# Mp100.net
KiCad netlist of a schematic drawn in Altium Designer
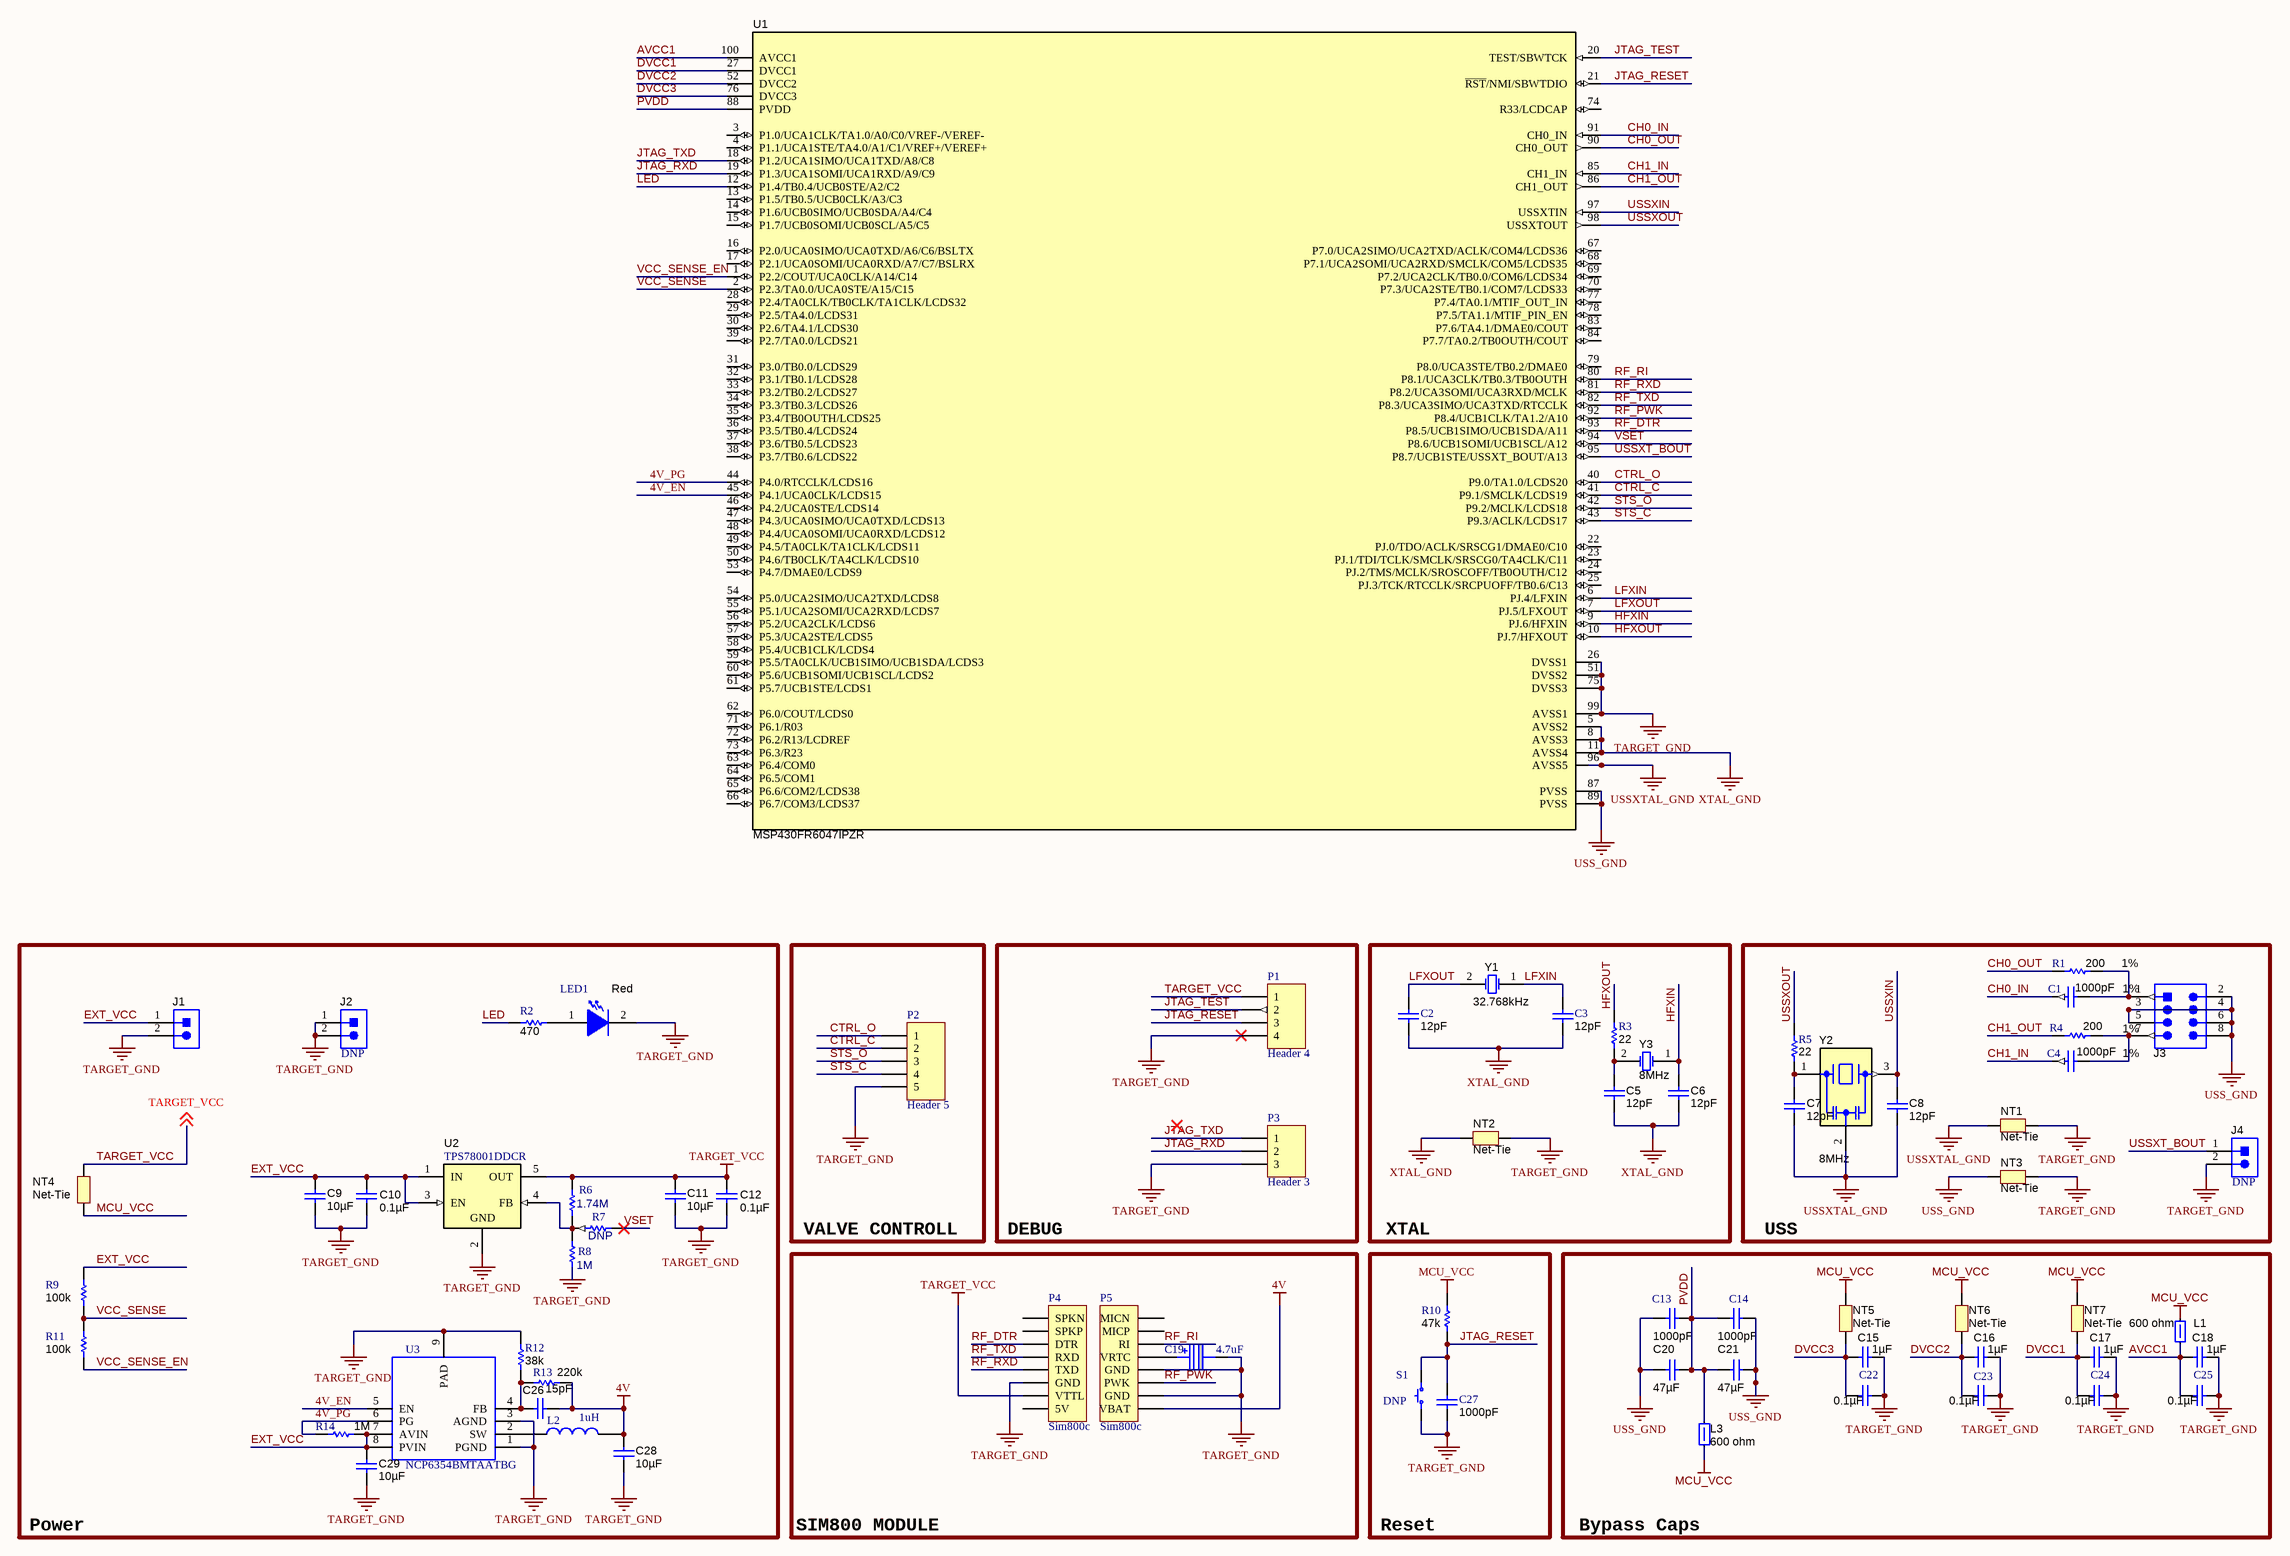
[diagram p0: Mp100.SchDoc]

(export (version "E")
  (design (tool "Eeschema 10.0.6"))
  (components
    (comp (ref "C1")
      (value "GRM1885C1H102FA01J")
      (footprint "CAPC1608X90N")
      (description "CAP, CERM, 1000 pF, 50 V, +/- 1%, C0G/NP0, 0603")
      (fields
        (field (name "VALUEDISPLAYED") "1000pF")
        (field (name "MANUFACTURER") "MuRata")
        (field (name "TOLERANCE_%") "1%")
        (field (name "PUBLISHER") "Texas Instruments")
      )
      (libsource (lib "Capacitor_Ceramic") (part "GRM1885C1H102FA01J"))
    )
    (comp (ref "C2")
      (value "GRM1555C1H120JA01D")
      (footprint "CAPC1005X55N")
      (description "CAP, CERM, 12 pF, 50 V, +/- 5%, C0G/NP0, 0402")
      (fields
        (field (name "VALUEDISPLAYED") "12pF")
        (field (name "MANUFACTURER") "MuRata")
        (field (name "PUBLISHER") "Texas Instruments")
      )
      (libsource (lib "Capacitor_Ceramic") (part "GRM1555C1H120JA01D"))
    )
    (comp (ref "C3")
      (value "GRM1555C1H120JA01D")
      (footprint "CAPC1005X55N")
      (description "CAP, CERM, 12 pF, 50 V, +/- 5%, C0G/NP0, 0402")
      (fields
        (field (name "VALUEDISPLAYED") "12pF")
        (field (name "MANUFACTURER") "MuRata")
        (field (name "PUBLISHER") "Texas Instruments")
      )
      (libsource (lib "Capacitor_Ceramic") (part "GRM1555C1H120JA01D"))
    )
    (comp (ref "C4")
      (value "GRM1885C1H102FA01J")
      (footprint "CAPC1608X90N")
      (description "CAP, CERM, 1000 pF, 50 V, +/- 1%, C0G/NP0, 0603")
      (fields
        (field (name "VALUEDISPLAYED") "1000pF")
        (field (name "MANUFACTURER") "MuRata")
        (field (name "TOLERANCE_%") "1%")
        (field (name "PUBLISHER") "Texas Instruments")
      )
      (libsource (lib "Capacitor_Ceramic") (part "GRM1885C1H102FA01J"))
    )
    (comp (ref "C5")
      (value "GRM1555C1H120JA01D")
      (footprint "CAPC1005X55N")
      (description "CAP, CERM, 12 pF, 50 V, +/- 5%, C0G/NP0, 0402")
      (fields
        (field (name "VALUEDISPLAYED") "12pF")
        (field (name "MANUFACTURER") "MuRata")
        (field (name "PUBLISHER") "Texas Instruments")
      )
      (libsource (lib "Capacitor_Ceramic") (part "GRM1555C1H120JA01D"))
    )
    (comp (ref "C6")
      (value "GRM1555C1H120JA01D")
      (footprint "CAPC1005X55N")
      (description "CAP, CERM, 12 pF, 50 V, +/- 5%, C0G/NP0, 0402")
      (fields
        (field (name "VALUEDISPLAYED") "12pF")
        (field (name "MANUFACTURER") "MuRata")
        (field (name "PUBLISHER") "Texas Instruments")
      )
      (libsource (lib "Capacitor_Ceramic") (part "GRM1555C1H120JA01D"))
    )
    (comp (ref "C7")
      (value "GRM1555C1H120JA01D")
      (footprint "CAPC1005X55N")
      (description "CAP, CERM, 12 pF, 50 V, +/- 5%, C0G/NP0, 0402")
      (fields
        (field (name "VALUEDISPLAYED") "12pF")
        (field (name "MANUFACTURER") "MuRata")
        (field (name "PUBLISHER") "Texas Instruments")
      )
      (libsource (lib "Capacitor_Ceramic") (part "GRM1555C1H120JA01D"))
    )
    (comp (ref "C8")
      (value "GRM1555C1H120JA01D")
      (footprint "CAPC1005X55N")
      (description "CAP, CERM, 12 pF, 50 V, +/- 5%, C0G/NP0, 0402")
      (fields
        (field (name "VALUEDISPLAYED") "12pF")
        (field (name "MANUFACTURER") "MuRata")
        (field (name "PUBLISHER") "Texas Instruments")
      )
      (libsource (lib "Capacitor_Ceramic") (part "GRM1555C1H120JA01D"))
    )
    (comp (ref "C9")
      (value "GRM188R61A106ME69D")
      (footprint "CAPC1608X90N")
      (description "CAP, CERM, 10 µF, 10 V, +/- 20%, X5R, 0603")
      (fields
        (field (name "VALUEDISPLAYED") "10µF")
        (field (name "MANUFACTURER") "MuRata")
        (field (name "PUBLISHER") "Texas Instruments")
      )
      (libsource (lib "Capacitor_Ceramic") (part "GRM188R61A106ME69D"))
    )
    (comp (ref "C10")
      (value "GRM155R71C104KA88D")
      (footprint "CAPC1005X55N")
      (description "CAP, CERM, 0.1 µF, 16 V, +/- 10%, X7R, 0402")
      (fields
        (field (name "VALUEDISPLAYED") "0.1µF")
        (field (name "MANUFACTURER") "MuRata")
        (field (name "PUBLISHER") "Texas Instruments")
      )
      (libsource (lib "Capacitor_Ceramic") (part "GRM155R71C104KA88D"))
    )
    (comp (ref "C11")
      (value "GRM188R61A106ME69D")
      (footprint "CAPC1608X90N")
      (description "CAP, CERM, 10 µF, 10 V, +/- 20%, X5R, 0603")
      (fields
        (field (name "VALUEDISPLAYED") "10µF")
        (field (name "MANUFACTURER") "MuRata")
        (field (name "PUBLISHER") "Texas Instruments")
      )
      (libsource (lib "Capacitor_Ceramic") (part "GRM188R61A106ME69D"))
    )
    (comp (ref "C12")
      (value "GRM155R71C104KA88D")
      (footprint "CAPC1005X55N")
      (description "CAP, CERM, 0.1 µF, 16 V, +/- 10%, X7R, 0402")
      (fields
        (field (name "VALUEDISPLAYED") "0.1µF")
        (field (name "MANUFACTURER") "MuRata")
        (field (name "PUBLISHER") "Texas Instruments")
      )
      (libsource (lib "Capacitor_Ceramic") (part "GRM155R71C104KA88D"))
    )
    (comp (ref "C13")
      (value "GRM1555C1H102JA01D")
      (footprint "CAPC1005X55N")
      (description "CAP, CERM, 1000 pF, 50 V, +/- 5%, C0G/NP0, 0402")
      (fields
        (field (name "VALUEDISPLAYED") "1000pF")
        (field (name "MANUFACTURER") "MuRata")
        (field (name "PUBLISHER") "Texas Instruments")
      )
      (libsource (lib "Capacitor_Ceramic") (part "GRM1555C1H102JA01D"))
    )
    (comp (ref "C14")
      (value "GRM1555C1H102JA01D")
      (footprint "CAPC1005X55N")
      (description "CAP, CERM, 1000 pF, 50 V, +/- 5%, C0G/NP0, 0402")
      (fields
        (field (name "VALUEDISPLAYED") "1000pF")
        (field (name "MANUFACTURER") "MuRata")
        (field (name "PUBLISHER") "Texas Instruments")
      )
      (libsource (lib "Capacitor_Ceramic") (part "GRM1555C1H102JA01D"))
    )
    (comp (ref "C15")
      (value "GRM188R71A105KA61D")
      (footprint "CAPC1608X90N")
      (description "CAP, CERM, 1 µF, 10 V, +/- 10%, X7R, 0603")
      (fields
        (field (name "VALUEDISPLAYED") "1µF")
        (field (name "MANUFACTURER") "MuRata")
        (field (name "PUBLISHER") "Texas Instruments")
      )
      (libsource (lib "Capacitor_Ceramic") (part "GRM188R71A105KA61D"))
    )
    (comp (ref "C16")
      (value "GRM188R71A105KA61D")
      (footprint "CAPC1608X90N")
      (description "CAP, CERM, 1 µF, 10 V, +/- 10%, X7R, 0603")
      (fields
        (field (name "VALUEDISPLAYED") "1µF")
        (field (name "MANUFACTURER") "MuRata")
        (field (name "PUBLISHER") "Texas Instruments")
      )
      (libsource (lib "Capacitor_Ceramic") (part "GRM188R71A105KA61D"))
    )
    (comp (ref "C17")
      (value "GRM188R71A105KA61D")
      (footprint "CAPC1608X90N")
      (description "CAP, CERM, 1 µF, 10 V, +/- 10%, X7R, 0603")
      (fields
        (field (name "VALUEDISPLAYED") "1µF")
        (field (name "MANUFACTURER") "MuRata")
        (field (name "PUBLISHER") "Texas Instruments")
      )
      (libsource (lib "Capacitor_Ceramic") (part "GRM188R71A105KA61D"))
    )
    (comp (ref "C18")
      (value "GRM188R71A105KA61D")
      (footprint "CAPC1608X90N")
      (description "CAP, CERM, 1 µF, 10 V, +/- 10%, X7R, 0603")
      (fields
        (field (name "VALUEDISPLAYED") "1µF")
        (field (name "MANUFACTURER") "MuRata")
        (field (name "PUBLISHER") "Texas Instruments")
      )
      (libsource (lib "Capacitor_Ceramic") (part "GRM188R71A105KA61D"))
    )
    (comp (ref "C19")
      (value "865090340001")
      (footprint "CAPAE430X550N")
      (fields (field (name "DISPLAYVALUE") "4.7uF"))
      (libsource (lib "865090340001") (part "865090340001"))
    )
    (comp (ref "C20")
      (value "GRM21BR60J476ME15L")
      (footprint "CAPC2012X145N")
      (description "CAP, CERM, 47 µF, 6.3 V, +/- 20%, X5R, 0805")
      (fields
        (field (name "VALUEDISPLAYED") "47µF")
        (field (name "MANUFACTURER") "MuRata")
        (field (name "PUBLISHER") "Texas Instruments")
      )
      (libsource (lib "Capacitor_Ceramic") (part "GRM21BR60J476ME15L"))
    )
    (comp (ref "C21")
      (value "GRM21BR60J476ME15L")
      (footprint "CAPC2012X145N")
      (description "CAP, CERM, 47 µF, 6.3 V, +/- 20%, X5R, 0805")
      (fields
        (field (name "VALUEDISPLAYED") "47µF")
        (field (name "MANUFACTURER") "MuRata")
        (field (name "PUBLISHER") "Texas Instruments")
      )
      (libsource (lib "Capacitor_Ceramic") (part "GRM21BR60J476ME15L"))
    )
    (comp (ref "C22")
      (value "GRM155R71C104KA88D")
      (footprint "CAPC1005X55N")
      (description "CAP, CERM, 0.1 µF, 16 V, +/- 10%, X7R, 0402")
      (fields
        (field (name "VALUEDISPLAYED") "0.1µF")
        (field (name "MANUFACTURER") "MuRata")
        (field (name "PUBLISHER") "Texas Instruments")
      )
      (libsource (lib "Capacitor_Ceramic") (part "GRM155R71C104KA88D"))
    )
    (comp (ref "C23")
      (value "GRM155R71C104KA88D")
      (footprint "CAPC1005X55N")
      (description "CAP, CERM, 0.1 µF, 16 V, +/- 10%, X7R, 0402")
      (fields
        (field (name "VALUEDISPLAYED") "0.1µF")
        (field (name "MANUFACTURER") "MuRata")
        (field (name "PUBLISHER") "Texas Instruments")
      )
      (libsource (lib "Capacitor_Ceramic") (part "GRM155R71C104KA88D"))
    )
    (comp (ref "C24")
      (value "GRM155R71C104KA88D")
      (footprint "CAPC1005X55N")
      (description "CAP, CERM, 0.1 µF, 16 V, +/- 10%, X7R, 0402")
      (fields
        (field (name "VALUEDISPLAYED") "0.1µF")
        (field (name "MANUFACTURER") "MuRata")
        (field (name "PUBLISHER") "Texas Instruments")
      )
      (libsource (lib "Capacitor_Ceramic") (part "GRM155R71C104KA88D"))
    )
    (comp (ref "C25")
      (value "GRM155R71C104KA88D")
      (footprint "CAPC1005X55N")
      (description "CAP, CERM, 0.1 µF, 16 V, +/- 10%, X7R, 0402")
      (fields
        (field (name "VALUEDISPLAYED") "0.1µF")
        (field (name "MANUFACTURER") "MuRata")
        (field (name "PUBLISHER") "Texas Instruments")
      )
      (libsource (lib "Capacitor_Ceramic") (part "GRM155R71C104KA88D"))
    )
    (comp (ref "C26")
      (value "GRM1555C1H120JA01D")
      (footprint "CAPC1005X55N")
      (description "CAP, CERM, 12 pF, 50 V, +/- 5%, C0G/NP0, 0402")
      (fields
        (field (name "VALUEDISPLAYED") "15pF")
        (field (name "MANUFACTURER") "MuRata")
        (field (name "PUBLISHER") "Texas Instruments")
      )
      (libsource (lib "Capacitor_Ceramic") (part "GRM1555C1H120JA01D"))
    )
    (comp (ref "C27")
      (value "GRM1555C1H102JA01D")
      (footprint "CAPC1005X55N")
      (description "CAP, CERM, 1000 pF, 50 V, +/- 5%, C0G/NP0, 0402")
      (fields
        (field (name "VALUEDISPLAYED") "1000pF")
        (field (name "MANUFACTURER") "MuRata")
        (field (name "PUBLISHER") "Texas Instruments")
      )
      (libsource (lib "Capacitor_Ceramic") (part "GRM1555C1H102JA01D"))
    )
    (comp (ref "C28")
      (value "GRM188R61A106ME69D")
      (footprint "CAPC1608X90N")
      (description "CAP, CERM, 10 µF, 10 V, +/- 20%, X5R, 0603")
      (fields
        (field (name "VALUEDISPLAYED") "10µF")
        (field (name "MANUFACTURER") "MuRata")
        (field (name "PUBLISHER") "Texas Instruments")
      )
      (libsource (lib "Capacitor_Ceramic") (part "GRM188R61A106ME69D"))
    )
    (comp (ref "C29")
      (value "GRM188R61A106ME69D")
      (footprint "CAPC1608X90N")
      (description "CAP, CERM, 10 µF, 10 V, +/- 20%, X5R, 0603")
      (fields
        (field (name "VALUEDISPLAYED") "10µF")
        (field (name "MANUFACTURER") "MuRata")
        (field (name "PUBLISHER") "Texas Instruments")
      )
      (libsource (lib "Capacitor_Ceramic") (part "GRM188R61A106ME69D"))
    )
    (comp (ref "J1")
      (value "TSW-102-07-G-S")
      (footprint "HDR1X2")
      (description "Header, 100mil, 2x1, Gold, TH")
      (fields
        (field (name "MANUFACTURER") "Samtec")
        (field (name "SYMBOLCREATOR") "a0412235")
        (field (name "PUBLISHER") "Texas Instruments")
      )
      (libsource (lib "Connectors_Samtec") (part "TSW-102-07-G-S"))
    )
    (comp (ref "J2")
      (value "TSW-102-07-G-S")
      (footprint "HDR1X2")
      (description "Header, 100mil, 2x1, Gold, TH")
      (fields
        (field (name "MANUFACTURER") "Samtec")
        (field (name "DNP") "DNP")
        (field (name "SYMBOLCREATOR") "a0412235")
        (field (name "PUBLISHER") "Texas Instruments")
      )
      (libsource (lib "Connectors_Samtec") (part "TSW-102-07-G-S"))
    )
    (comp (ref "J3")
      (value "TSW-104-07-G-D")
      (footprint "HDR2X4")
      (description "Header, 100mil, 4x2, Gold, TH")
      (fields
        (field (name "MANUFACTURER") "Samtec")
        (field (name "SYMBOLCREATOR") "a0411947")
        (field (name "PUBLISHER") "Texas Instruments")
      )
      (libsource (lib "Connectors_Samtec") (part "TSW-104-07-G-D"))
    )
    (comp (ref "J4")
      (value "HMTSW-102-07-G-S-240")
      (footprint "HDR1X2")
      (description "Header, 100mil, 2x1, Gold, TH")
      (fields
        (field (name "MANUFACTURER") "Samtec")
        (field (name "DNP") "DNP")
        (field (name "SYMBOLCREATOR") "a0412235")
        (field (name "PUBLISHER") "Texas Instruments")
      )
      (libsource (lib "Connectors_Samtec") (part "HMTSW-102-07-G-S-240"))
    )
    (comp (ref "L1")
      (value "600 ohm")
      (footprint "6-0805_L")
      (description "Ferrite Bead, 600 ohm @ 100 MHz, 2 A, 0805")
      (fields
        (field (name "PARTNUMBER") "MPZ2012S601A")
        (field (name "MANUFACTURER") "TDK")
        (field (name "PUBLISHER") "Texas Instruments")
      )
      (libsource (lib "FerriteBead") (part "MPZ2012S601A"))
    )
    (comp (ref "L2")
      (value "1uH")
      (footprint "INDM4040X180N")
      (description "Murata LQH44P_P0 Series Shielded Wire-wound SMD Inductor 1 H 30% 2950mA Idc")
      (fields (field (name "MANUFACTURER_PART_NUMBER") "LQH44PN1R0NP0L"))
      (libsource (lib "LQH44PN1R0NP0L") (part "LQH44PN1R0NP0L"))
    )
    (comp (ref "L3")
      (value "600 ohm")
      (footprint "6-0805_L")
      (description "Ferrite Bead, 600 ohm @ 100 MHz, 2 A, 0805")
      (fields
        (field (name "PARTNUMBER") "MPZ2012S601A")
        (field (name "MANUFACTURER") "TDK")
        (field (name "PUBLISHER") "Texas Instruments")
      )
      (libsource (lib "") (part "MPZ2012S601A_1"))
    )
    (comp (ref "LED1")
      (value "Red")
      (footprint "LEDC1608X90N")
      (description "LED, Red, SMD")
      (fields
        (field (name "MANUFACTURER") "Lite-On")
        (field (name "PARTNUMBER") "LTST-C190CKT")
        (field (name "PUBLISHER") "Texas Instruments")
      )
      (libsource (lib "LED") (part "LTST-C190CKT"))
    )
    (comp (ref "NT1")
      (value "Net-Tie")
      (footprint "2way_MP")
      (description "Single point connection between nets.")
      (fields (field (name "SYMBOLCREATOR") "codlsc") (field (name "PUBLISHER") "Texas Instruments"))
      (libsource (lib "MiscParts") (part "Net-Tie"))
    )
    (comp (ref "NT2")
      (value "Net-Tie")
      (footprint "2way_MP")
      (description "Single point connection between nets.")
      (fields (field (name "SYMBOLCREATOR") "codlsc") (field (name "PUBLISHER") "Texas Instruments"))
      (libsource (lib "MiscParts") (part "Net-Tie"))
    )
    (comp (ref "NT3")
      (value "Net-Tie")
      (footprint "2way_MP")
      (description "Single point connection between nets.")
      (fields (field (name "SYMBOLCREATOR") "codlsc") (field (name "PUBLISHER") "Texas Instruments"))
      (libsource (lib "MiscParts") (part "Net-Tie"))
    )
    (comp (ref "NT4")
      (value "Net-Tie")
      (footprint "2way_MP")
      (description "Single point connection between nets.")
      (fields (field (name "SYMBOLCREATOR") "codlsc") (field (name "PUBLISHER") "Texas Instruments"))
      (libsource (lib "") (part "Net-Tie_1"))
    )
    (comp (ref "NT5")
      (value "Net-Tie")
      (footprint "2way_MP")
      (description "Single point connection between nets.")
      (fields (field (name "SYMBOLCREATOR") "codlsc") (field (name "PUBLISHER") "Texas Instruments"))
      (libsource (lib "") (part "Net-Tie_1"))
    )
    (comp (ref "NT6")
      (value "Net-Tie")
      (footprint "2way_MP")
      (description "Single point connection between nets.")
      (fields (field (name "SYMBOLCREATOR") "codlsc") (field (name "PUBLISHER") "Texas Instruments"))
      (libsource (lib "") (part "Net-Tie_1"))
    )
    (comp (ref "NT7")
      (value "Net-Tie")
      (footprint "2way_MP")
      (description "Single point connection between nets.")
      (fields (field (name "SYMBOLCREATOR") "codlsc") (field (name "PUBLISHER") "Texas Instruments"))
      (libsource (lib "") (part "Net-Tie_1"))
    )
    (comp (ref "P1")
      (value "Header 4")
      (footprint "HDR1X4")
      (description "Header, 4-Pin")
      (fields (field (name "PUBLISHER") "Altium Limited"))
      (libsource (lib "Miscellaneous Connectors") (part "Header 4"))
    )
    (comp (ref "P2")
      (value "Header 5")
      (footprint "HDR1X5")
      (description "Header, 5-Pin")
      (fields (field (name "PUBLISHER") "Altium Limited"))
      (libsource (lib "Miscellaneous Connectors") (part "Header 5"))
    )
    (comp (ref "P3")
      (value "Header 3")
      (footprint "HDR1X3")
      (description "Header, 3-Pin")
      (fields (field (name "PUBLISHER") "Altium Limited"))
      (libsource (lib "Miscellaneous Connectors") (part "Header 3"))
    )
    (comp (ref "P4")
      (value "Sim800c")
      (footprint "HDR1X8")
      (description "Header, 8-Pin")
      (fields (field (name "PUBLISHER") "Altium Limited"))
      (libsource (lib "") (part "Header 8_1"))
    )
    (comp (ref "P5")
      (value "Sim800c")
      (footprint "HDR1X8")
      (description "Header, 8-Pin")
      (fields (field (name "PUBLISHER") "Altium Limited"))
      (libsource (lib "Miscellaneous Connectors") (part "Header 8"))
    )
    (comp (ref "R1")
      (value "CRCW0402200RFKED")
      (footprint "RESC1005X40N")
      (description "RES, 200, 1%, 0.063 W, 0402")
      (fields
        (field (name "VALUEDISPLAYED") "200")
        (field (name "MANUFACTURER") "Vishay-Dale")
        (field (name "VALUE1") "1%")
        (field (name "PUBLISHER") "Texas Instruments")
      )
      (libsource (lib "Resistor_0402") (part "CRCW0402200RFKED"))
    )
    (comp (ref "R2")
      (value "CRCW0402470RJNED")
      (footprint "RESC1005X40N")
      (description "RES, 470, 5%, 0.063 W, 0402")
      (fields
        (field (name "VALUEDISPLAYED") "470")
        (field (name "MANUFACTURER") "Vishay-Dale")
        (field (name "PUBLISHER") "Texas Instruments")
      )
      (libsource (lib "Resistor_0402") (part "CRCW0402470RJNED"))
    )
    (comp (ref "R3")
      (value "CRCW040222R0JNED")
      (footprint "RESC1005X40N")
      (description "RES, 22, 5%, 0.063 W, 0402")
      (fields
        (field (name "VALUEDISPLAYED") "22")
        (field (name "MANUFACTURER") "Vishay-Dale")
        (field (name "PUBLISHER") "Texas Instruments")
      )
      (libsource (lib "Resistor_0402") (part "CRCW040222R0JNED"))
    )
    (comp (ref "R4")
      (value "CRCW0402200RFKED")
      (footprint "RESC1005X40N")
      (description "RES, 200, 1%, 0.063 W, 0402")
      (fields
        (field (name "VALUEDISPLAYED") "200")
        (field (name "MANUFACTURER") "Vishay-Dale")
        (field (name "VALUE1") "1%")
        (field (name "PUBLISHER") "Texas Instruments")
      )
      (libsource (lib "Resistor_0402") (part "CRCW0402200RFKED"))
    )
    (comp (ref "R5")
      (value "CRCW040222R0JNED")
      (footprint "RESC1005X40N")
      (description "RES, 22, 5%, 0.063 W, 0402")
      (fields
        (field (name "VALUEDISPLAYED") "22")
        (field (name "MANUFACTURER") "Vishay-Dale")
        (field (name "PUBLISHER") "Texas Instruments")
      )
      (libsource (lib "Resistor_0402") (part "CRCW040222R0JNED"))
    )
    (comp (ref "R6")
      (value "1.74M")
      (footprint "RESC1005X40N")
      (description "RES, 0, 5%, 0.063 W, 0402")
      (fields
        (field (name "PARTNUMBER") "CRCW04021M74FKED")
        (field (name "MANUFACTURER") "Used in BOM report")
        (field (name "PUBLISHER") "Texas Instruments")
      )
      (libsource (lib "MiscParts") (part "Resistor"))
    )
    (comp (ref "R7")
      (value "DNP")
      (footprint "RESC1005X40N")
      (description "RES, 0, 5%, 0.063 W, 0402")
      (fields
        (field (name "MANUFACTURER") "Used in BOM report")
        (field (name "PUBLISHER") "Texas Instruments")
      )
      (libsource (lib "MiscParts") (part "Resistor"))
    )
    (comp (ref "R8")
      (value "1M")
      (footprint "RESC1005X40N")
      (description "RES 1M OHM 1% 1/16W 0402")
      (fields
        (field (name "PARTNUMBER") "CRCW04021M00JNED")
        (field (name "MANUFACTURER") "Used in BOM report")
        (field (name "PUBLISHER") "Texas Instruments")
      )
      (libsource (lib "MiscParts") (part "Resistor"))
    )
    (comp (ref "R9")
      (value "CRCW0402100KJNED")
      (footprint "RESC1005X40N")
      (description "RES, 100 k, 5%, 0.063 W, 0402")
      (fields
        (field (name "VALUEDISPLAYED") "100k")
        (field (name "MANUFACTURER") "Vishay-Dale")
        (field (name "PUBLISHER") "Texas Instruments")
      )
      (libsource (lib "Resistor_0402") (part "CRCW0402100KJNED"))
    )
    (comp (ref "R10")
      (value "CRCW040247K0JNED")
      (footprint "RESC1005X40N")
      (description "RES, 47 k, 5%, 0.063 W, 0402")
      (fields
        (field (name "VALUEDISPLAYED") "47k")
        (field (name "MANUFACTURER") "Vishay-Dale")
        (field (name "PUBLISHER") "Texas Instruments")
      )
      (libsource (lib "Resistor_0402") (part "CRCW040247K0JNED"))
    )
    (comp (ref "R11")
      (value "CRCW0402100KJNED")
      (footprint "RESC1005X40N")
      (description "RES, 100 k, 5%, 0.063 W, 0402")
      (fields
        (field (name "VALUEDISPLAYED") "100k")
        (field (name "MANUFACTURER") "Vishay-Dale")
        (field (name "PUBLISHER") "Texas Instruments")
      )
      (libsource (lib "Resistor_0402") (part "CRCW0402100KJNED"))
    )
    (comp (ref "R12")
      (value "CRCW0402470RJNED")
      (footprint "RESC1005X40N")
      (description "RES, 470, 5%, 0.063 W, 0402")
      (fields
        (field (name "VALUEDISPLAYED") "38k")
        (field (name "MANUFACTURER") "Vishay-Dale")
        (field (name "PUBLISHER") "Texas Instruments")
      )
      (libsource (lib "Resistor_0402") (part "CRCW0402470RJNED"))
    )
    (comp (ref "R13")
      (value "CRCW0402470RJNED")
      (footprint "RESC1005X40N")
      (description "RES, 470, 5%, 0.063 W, 0402")
      (fields
        (field (name "VALUEDISPLAYED") "220k")
        (field (name "MANUFACTURER") "Vishay-Dale")
        (field (name "PUBLISHER") "Texas Instruments")
      )
      (libsource (lib "Resistor_0402") (part "CRCW0402470RJNED"))
    )
    (comp (ref "R14")
      (value "CRCW0402100KJNED")
      (footprint "RESC1005X40N")
      (description "RES, 100 k, 5%, 0.063 W, 0402")
      (fields
        (field (name "VALUEDISPLAYED") "1M")
        (field (name "MANUFACTURER") "Vishay-Dale")
        (field (name "PUBLISHER") "Texas Instruments")
      )
      (libsource (lib "Resistor_0402") (part "CRCW0402100KJNED"))
    )
    (comp (ref "S1")
      (value "SPST-NO")
      (footprint "HDR1X2")
      (fields (field (name "PLACMENT") "DNP"))
      (libsource (lib "Button") (part "NKK AB11AH-HA"))
    )
    (comp (ref "U1")
      (value "MSP430FR6047IPZR")
      (footprint "QFP50P1600X1600X160-100N")
      (description "Mixed-Signal Microcontroller, PZ0100A (LQFP-100)")
      (fields
        (field (name "ALTERNATE PARTNUMBER") "MSP430FR6047IPZ")
        (field (name "MANUFACTURER") "Texas Instruments")
        (field (name "SYMBOLCREATOR") "Altium")
        (field (name "PUBLISHER") "Texas Instruments")
      )
      (libsource (lib "TI_Pre_RTM") (part "MSP430FR6047IPZR"))
    )
    (comp (ref "U2")
      (value "TPS78001DDCR")
      (footprint "SOT95P280X145-5N")
      (fields
        (field (name "MANUFACTURER") "Texas Instruments")
        (field (name "ALTERNATE PARTNUMBER") "Equivalent")
      )
      (libsource (lib "TI Power Management Linear Regulator Single Channel LDO (0-350mA)") (part "TPS78001DDCR"))
    )
    (comp (ref "U3")
      (value "NCP6354BMTAATBG")
      (footprint "SON50P200X200X80-9N-D")
      (libsource (lib "NCP6354BMTAATBG") (part "NCP6354BMTAATBG"))
    )
    (comp (ref "Y1")
      (value "ABS07-32.768KHZ-9-T")
      (footprint "ABS-07")
      (description "CRYSTAL, 32.768KHZ, 9PF, SMD")
      (fields
        (field (name "FREQUENCY") "32.768kHz")
        (field (name "MANUFACTURER") "Abracon Corporation")
        (field (name "SYMBOLCREATOR") "a0412235")
        (field (name "PUBLISHER") "Texas Instruments")
      )
      (libsource (lib "Oscillators") (part "ABS07-32.768KHZ-9-T"))
    )
    (comp (ref "Y2")
      (value "AWSCR-8.00CV-T")
      (footprint "Abracon_AWSCR-8.00CV-T_0")
      (description "Ceramic Resonator, 8MHz, 22pF, SMD")
      (fields
        (field (name "FREQUENCY") "8MHz")
        (field (name "MANUFACTURER") "Abracon Corporation")
        (field (name "SYMBOLCREATOR") "a0799721")
        (field (name "PUBLISHER") "Texas Instruments")
      )
      (libsource (lib "Oscillators") (part "AWSCR-8.00CV-T"))
    )
    (comp (ref "Y3")
      (value "ABM3-8.000MHZ-D2Y-T")
      (footprint "ABM38000MHzD2YT")
      (description "Crystal, 8MHz, SMD")
      (fields
        (field (name "FREQUENCY") "8MHz")
        (field (name "MANUFACTURER") "Abracon Corporation")
        (field (name "SYMBOLCREATOR") "a0412235")
        (field (name "PUBLISHER") "Texas Instruments")
      )
      (libsource (lib "Oscillators") (part "ABM3-8.000MHZ-D2Y-T"))
    )
  )
  (nets
    (net (code "1") (name "/4V_EN") (class "Default")
      (node (ref "U1") (pin "45") (pinfunction "P4.1/UCA0CLK/LCDS15_45") (pintype "bidirectional"))
      (node (ref "U3") (pin "5") (pinfunction "EN_5") (pintype "passive"))
    )
    (net (code "2") (name "/4V_PG") (class "Default")
      (node (ref "R14") (pin "2") (pinfunction "2_2") (pintype "passive"))
      (node (ref "U1") (pin "44") (pinfunction "P4.0/RTCCLK/LCDS16_44") (pintype "bidirectional"))
      (node (ref "U3") (pin "6") (pinfunction "PG_6") (pintype "passive"))
    )
    (net (code "3") (name "/AVCC1") (class "Default")
      (node (ref "C18") (pin "1") (pinfunction "1_1") (pintype "passive"))
      (node (ref "C25") (pin "1") (pinfunction "1_1") (pintype "passive"))
      (node (ref "L1") (pin "1") (pinfunction "1_1") (pintype "passive"))
      (node (ref "U1") (pin "100") (pinfunction "AVCC1_100") (pintype "power_in"))
    )
    (net (code "4") (name "/CH0_IN") (class "Default")
      (node (ref "C1") (pin "1") (pinfunction "1_1") (pintype "output"))
      (node (ref "U1") (pin "91") (pinfunction "CH0_IN_91") (pintype "input"))
    )
    (net (code "5") (name "/CH0_OUT") (class "Default")
      (node (ref "R1") (pin "2") (pinfunction "2_2") (pintype "passive"))
      (node (ref "U1") (pin "90") (pinfunction "CH0_OUT_90") (pintype "output"))
    )
    (net (code "6") (name "/CH1_IN") (class "Default")
      (node (ref "C4") (pin "1") (pinfunction "1_1") (pintype "output"))
      (node (ref "U1") (pin "85") (pinfunction "CH1_IN_85") (pintype "input"))
    )
    (net (code "7") (name "/CH1_OUT") (class "Default")
      (node (ref "R4") (pin "2") (pinfunction "2_2") (pintype "passive"))
      (node (ref "U1") (pin "86") (pinfunction "CH1_OUT_86") (pintype "output"))
    )
    (net (code "8") (name "/CTRL_C") (class "Default")
      (node (ref "P2") (pin "2") (pinfunction "2_2") (pintype "passive"))
      (node (ref "U1") (pin "41") (pinfunction "P9.1/SMCLK/LCDS19_41") (pintype "bidirectional"))
    )
    (net (code "9") (name "/CTRL_O") (class "Default")
      (node (ref "P2") (pin "1") (pinfunction "1_1") (pintype "passive"))
      (node (ref "U1") (pin "40") (pinfunction "P9.0/TA1.0/LCDS20_40") (pintype "bidirectional"))
    )
    (net (code "10") (name "/DVCC1") (class "Default")
      (node (ref "C17") (pin "1") (pinfunction "1_1") (pintype "passive"))
      (node (ref "C24") (pin "2") (pinfunction "2_2") (pintype "passive"))
      (node (ref "NT7") (pin "1") (pinfunction "1_1") (pintype "passive"))
      (node (ref "U1") (pin "27") (pinfunction "DVCC1_27") (pintype "power_in"))
    )
    (net (code "11") (name "/DVCC2") (class "Default")
      (node (ref "C16") (pin "2") (pinfunction "2_2") (pintype "passive"))
      (node (ref "C23") (pin "1") (pinfunction "1_1") (pintype "passive"))
      (node (ref "NT6") (pin "1") (pinfunction "1_1") (pintype "passive"))
      (node (ref "U1") (pin "52") (pinfunction "DVCC2_52") (pintype "power_in"))
    )
    (net (code "12") (name "/DVCC3") (class "Default")
      (node (ref "C15") (pin "1") (pinfunction "1_1") (pintype "passive"))
      (node (ref "C22") (pin "1") (pinfunction "1_1") (pintype "passive"))
      (node (ref "NT5") (pin "1") (pinfunction "1_1") (pintype "passive"))
      (node (ref "U1") (pin "76") (pinfunction "DVCC3_76") (pintype "power_in"))
    )
    (net (code "13") (name "/EXT_VCC") (class "Default")
      (node (ref "C10") (pin "1") (pinfunction "1_1") (pintype "passive"))
      (node (ref "C29") (pin "1") (pinfunction "1_1") (pintype "passive"))
      (node (ref "C9") (pin "1") (pinfunction "1_1") (pintype "passive"))
      (node (ref "J1") (pin "1") (pinfunction "1_1") (pintype "passive"))
      (node (ref "R14") (pin "1") (pinfunction "1_1") (pintype "passive"))
      (node (ref "R9") (pin "2") (pinfunction "2_2") (pintype "passive"))
      (node (ref "U2") (pin "1") (pinfunction "IN_1") (pintype "power_in"))
      (node (ref "U2") (pin "3") (pinfunction "EN_3") (pintype "input"))
      (node (ref "U3") (pin "7") (pinfunction "AVIN_7") (pintype "power_in"))
      (node (ref "U3") (pin "8") (pinfunction "PVIN_8") (pintype "power_in"))
    )
    (net (code "14") (name "/HFXIN") (class "Default")
      (node (ref "C6") (pin "1") (pinfunction "1_1") (pintype "passive"))
      (node (ref "U1") (pin "9") (pinfunction "PJ.6/HFXIN_9") (pintype "bidirectional"))
      (node (ref "Y3") (pin "1") (pinfunction "OSC1_1") (pintype "passive"))
    )
    (net (code "15") (name "/HFXOUT") (class "Default")
      (node (ref "R3") (pin "2") (pinfunction "2_2") (pintype "passive"))
      (node (ref "U1") (pin "10") (pinfunction "PJ.7/HFXOUT_10") (pintype "bidirectional"))
    )
    (net (code "16") (name "/JTAG_RESET") (class "Default")
      (node (ref "C27") (pin "1") (pinfunction "1_1") (pintype "passive"))
      (node (ref "P1") (pin "3") (pinfunction "3_3") (pintype "passive"))
      (node (ref "R10") (pin "1") (pinfunction "1_1") (pintype "passive"))
      (node (ref "S1") (pin "3") (pinfunction "3_3") (pintype "passive"))
      (node (ref "U1") (pin "21") (pinfunction "~{RST}/NMI/SBWTDIO_21") (pintype "bidirectional"))
    )
    (net (code "17") (name "/JTAG_RXD") (class "Default")
      (node (ref "P3") (pin "2") (pinfunction "2_2") (pintype "passive"))
      (node (ref "U1") (pin "19") (pinfunction "P1.3/UCA1SOMI/UCA1RXD/A9/C9_19") (pintype "bidirectional"))
    )
    (net (code "18") (name "/JTAG_TEST") (class "Default")
      (node (ref "P1") (pin "2") (pinfunction "2_2") (pintype "output"))
      (node (ref "U1") (pin "20") (pinfunction "TEST/SBWTCK_20") (pintype "input"))
    )
    (net (code "19") (name "/JTAG_TXD") (class "Default")
      (node (ref "P3") (pin "1") (pinfunction "1_1") (pintype "passive"))
      (node (ref "U1") (pin "18") (pinfunction "P1.2/UCA1SIMO/UCA1TXD/A8/C8_18") (pintype "bidirectional"))
    )
    (net (code "20") (name "/LED") (class "Default")
      (node (ref "R2") (pin "1") (pinfunction "1_1") (pintype "passive"))
      (node (ref "U1") (pin "12") (pinfunction "P1.4/TB0.4/UCB0STE/A2/C2_12") (pintype "bidirectional"))
    )
    (net (code "21") (name "/LFXIN") (class "Default")
      (node (ref "C3") (pin "1") (pinfunction "1_1") (pintype "passive"))
      (node (ref "U1") (pin "6") (pinfunction "PJ.4/LFXIN_6") (pintype "bidirectional"))
      (node (ref "Y1") (pin "1") (pinfunction "OSC1_1") (pintype "passive"))
    )
    (net (code "22") (name "/LFXOUT") (class "Default")
      (node (ref "C2") (pin "2") (pinfunction "2_2") (pintype "passive"))
      (node (ref "U1") (pin "7") (pinfunction "PJ.5/LFXOUT_7") (pintype "bidirectional"))
      (node (ref "Y1") (pin "2") (pinfunction "OSC2_2") (pintype "passive"))
    )
    (net (code "23") (name "/PVDD") (class "Default")
      (node (ref "C13") (pin "1") (pinfunction "1_1") (pintype "passive"))
      (node (ref "C14") (pin "2") (pinfunction "2_2") (pintype "passive"))
      (node (ref "C20") (pin "2") (pinfunction "2_2") (pintype "passive"))
      (node (ref "C21") (pin "1") (pinfunction "1_1") (pintype "passive"))
      (node (ref "L3") (pin "1") (pinfunction "1_1") (pintype "passive"))
      (node (ref "U1") (pin "88") (pinfunction "PVDD_88") (pintype "power_in"))
    )
    (net (code "24") (name "/RF_DTR") (class "Default")
      (node (ref "P4") (pin "3") (pinfunction "DTR_3") (pintype "passive"))
      (node (ref "U1") (pin "93") (pinfunction "P8.5/UCB1SIMO/UCB1SDA/A11_93") (pintype "bidirectional"))
    )
    (net (code "25") (name "/RF_PWK") (class "Default")
      (node (ref "P5") (pin "3") (pinfunction "PWK_3") (pintype "passive"))
      (node (ref "U1") (pin "92") (pinfunction "P8.4/UCB1CLK/TA1.2/A10_92") (pintype "bidirectional"))
    )
    (net (code "26") (name "/RF_RI") (class "Default")
      (node (ref "P5") (pin "6") (pinfunction "RI_6") (pintype "passive"))
      (node (ref "U1") (pin "80") (pinfunction "P8.1/UCA3CLK/TB0.3/TB0OUTH_80") (pintype "bidirectional"))
    )
    (net (code "27") (name "/RF_RXD") (class "Default")
      (node (ref "P4") (pin "5") (pinfunction "TXD_5") (pintype "passive"))
      (node (ref "U1") (pin "81") (pinfunction "P8.2/UCA3SOMI/UCA3RXD/MCLK_81") (pintype "bidirectional"))
    )
    (net (code "28") (name "/RF_TXD") (class "Default")
      (node (ref "P4") (pin "4") (pinfunction "RXD_4") (pintype "passive"))
      (node (ref "U1") (pin "82") (pinfunction "P8.3/UCA3SIMO/UCA3TXD/RTCCLK_82") (pintype "bidirectional"))
    )
    (net (code "29") (name "/STS_C") (class "Default")
      (node (ref "P2") (pin "4") (pinfunction "4_4") (pintype "passive"))
      (node (ref "U1") (pin "43") (pinfunction "P9.3/ACLK/LCDS17_43") (pintype "bidirectional"))
    )
    (net (code "30") (name "/STS_O") (class "Default")
      (node (ref "P2") (pin "3") (pinfunction "3_3") (pintype "passive"))
      (node (ref "U1") (pin "42") (pinfunction "P9.2/MCLK/LCDS18_42") (pintype "bidirectional"))
    )
    (net (code "31") (name "/USSXIN") (class "Default")
      (node (ref "C8") (pin "1") (pinfunction "1_1") (pintype "passive"))
      (node (ref "U1") (pin "97") (pinfunction "USSXTIN_97") (pintype "input"))
      (node (ref "Y2") (pin "3") (pinfunction "Out_3") (pintype "output"))
    )
    (net (code "32") (name "/USSXOUT") (class "Default")
      (node (ref "R5") (pin "2") (pinfunction "2_2") (pintype "passive"))
      (node (ref "U1") (pin "98") (pinfunction "USSXTOUT_98") (pintype "output"))
    )
    (net (code "33") (name "/USSXT_BOUT") (class "Default")
      (node (ref "J4") (pin "1") (pinfunction "1_1") (pintype "passive"))
      (node (ref "U1") (pin "95") (pinfunction "P8.7/UCB1STE/USSXT_BOUT/A13_95") (pintype "bidirectional"))
    )
    (net (code "34") (name "/VCC_SENSE") (class "Default")
      (node (ref "R11") (pin "2") (pinfunction "2_2") (pintype "passive"))
      (node (ref "R9") (pin "1") (pinfunction "1_1") (pintype "passive"))
      (node (ref "U1") (pin "2") (pinfunction "P2.3/TA0.0/UCA0STE/A15/C15_2") (pintype "bidirectional"))
    )
    (net (code "35") (name "/VCC_SENSE_EN") (class "Default")
      (node (ref "R11") (pin "1") (pinfunction "1_1") (pintype "passive"))
      (node (ref "U1") (pin "1") (pinfunction "P2.2/COUT/UCA0CLK/A14/C14_1") (pintype "bidirectional"))
    )
    (net (code "36") (name "/VSET") (class "Default")
      (node (ref "R7") (pin "1") (pinfunction "1_1") (pintype "passive"))
      (node (ref "U1") (pin "94") (pinfunction "P8.6/UCB1SOMI/UCB1SCL/A12_94") (pintype "bidirectional"))
    )
    (net (code "37") (name "4V") (class "Default")
      (node (ref "C26") (pin "2") (pinfunction "2_2") (pintype "passive"))
      (node (ref "C28") (pin "1") (pinfunction "1_1") (pintype "passive"))
      (node (ref "L2") (pin "2") (pinfunction "2_2") (pintype "passive"))
      (node (ref "P5") (pin "1") (pinfunction "VBAT_1") (pintype "passive"))
      (node (ref "R13") (pin "2") (pinfunction "2_2") (pintype "passive"))
    )
    (net (code "38") (name "MCU_VCC") (class "Default")
      (node (ref "L1") (pin "2") (pinfunction "2_2") (pintype "passive"))
      (node (ref "L3") (pin "2") (pinfunction "2_2") (pintype "passive"))
      (node (ref "NT4") (pin "1") (pinfunction "1_1") (pintype "passive"))
      (node (ref "NT5") (pin "2") (pinfunction "2_2") (pintype "passive"))
      (node (ref "NT6") (pin "2") (pinfunction "2_2") (pintype "passive"))
      (node (ref "NT7") (pin "2") (pinfunction "2_2") (pintype "passive"))
      (node (ref "R10") (pin "2") (pinfunction "2_2") (pintype "passive"))
    )
    (net (code "39") (name "Net-(C1-Pad2)") (class "Default")
      (node (ref "C1") (pin "2") (pinfunction "2_2") (pintype "passive"))
      (node (ref "J3") (pin "1") (pinfunction "1_1") (pintype "output"))
      (node (ref "R1") (pin "1") (pinfunction "1_1") (pintype "passive"))
    )
    (net (code "40") (name "Net-(C4-Pad2)") (class "Default")
      (node (ref "C4") (pin "2") (pinfunction "2_2") (pintype "passive"))
      (node (ref "J3") (pin "7") (pinfunction "7_7") (pintype "output"))
      (node (ref "R4") (pin "1") (pinfunction "1_1") (pintype "passive"))
    )
    (net (code "41") (name "Net-(C19-+)") (class "Default")
      (node (ref "C19") (pin "1") (pinfunction "+_1") (pintype "passive"))
      (node (ref "P5") (pin "5") (pinfunction "VRTC_5") (pintype "passive"))
    )
    (net (code "42") (name "Net-(LED1-A)") (class "Default")
      (node (ref "LED1") (pin "1") (pinfunction "A_1") (pintype "passive"))
      (node (ref "R2") (pin "2") (pinfunction "2_2") (pintype "passive"))
    )
    (net (code "43") (name "Net-(U2-FB)") (class "Default")
      (node (ref "R6") (pin "1") (pinfunction "1_1") (pintype "passive"))
      (node (ref "R7") (pin "2") (pinfunction "2_2") (pintype "passive"))
      (node (ref "R8") (pin "2") (pinfunction "2_2") (pintype "passive"))
      (node (ref "U2") (pin "4") (pinfunction "FB_4") (pintype "input"))
    )
    (net (code "44") (name "Net-(U3-FB)") (class "Default")
      (node (ref "C26") (pin "1") (pinfunction "1_1") (pintype "passive"))
      (node (ref "R12") (pin "2") (pinfunction "2_2") (pintype "passive"))
      (node (ref "R13") (pin "1") (pinfunction "1_1") (pintype "passive"))
      (node (ref "U3") (pin "4") (pinfunction "FB_4") (pintype "passive"))
    )
    (net (code "45") (name "Net-(U3-SW)") (class "Default")
      (node (ref "L2") (pin "1") (pinfunction "1_1") (pintype "passive"))
      (node (ref "U3") (pin "2") (pinfunction "SW_2") (pintype "power_in"))
    )
    (net (code "46") (name "Net-(Y2-In)") (class "Default")
      (node (ref "C7") (pin "1") (pinfunction "1_1") (pintype "passive"))
      (node (ref "R5") (pin "1") (pinfunction "1_1") (pintype "passive"))
      (node (ref "Y2") (pin "1") (pinfunction "In_1") (pintype "passive"))
    )
    (net (code "47") (name "Net-(Y3-OSC2)") (class "Default")
      (node (ref "C5") (pin "1") (pinfunction "1_1") (pintype "passive"))
      (node (ref "R3") (pin "1") (pinfunction "1_1") (pintype "passive"))
      (node (ref "Y3") (pin "2") (pinfunction "OSC2_2") (pintype "passive"))
    )
    (net (code "48") (name "TARGET_GND") (class "Default")
      (node (ref "C10") (pin "2") (pinfunction "2_2") (pintype "passive"))
      (node (ref "C11") (pin "2") (pinfunction "2_2") (pintype "passive"))
      (node (ref "C12") (pin "2") (pinfunction "2_2") (pintype "passive"))
      (node (ref "C15") (pin "2") (pinfunction "2_2") (pintype "passive"))
      (node (ref "C16") (pin "1") (pinfunction "1_1") (pintype "passive"))
      (node (ref "C17") (pin "2") (pinfunction "2_2") (pintype "passive"))
      (node (ref "C18") (pin "2") (pinfunction "2_2") (pintype "passive"))
      (node (ref "C19") (pin "2") (pinfunction "-_2") (pintype "passive"))
      (node (ref "C22") (pin "2") (pinfunction "2_2") (pintype "passive"))
      (node (ref "C23") (pin "2") (pinfunction "2_2") (pintype "passive"))
      (node (ref "C24") (pin "1") (pinfunction "1_1") (pintype "passive"))
      (node (ref "C25") (pin "2") (pinfunction "2_2") (pintype "passive"))
      (node (ref "C27") (pin "2") (pinfunction "2_2") (pintype "passive"))
      (node (ref "C28") (pin "2") (pinfunction "2_2") (pintype "passive"))
      (node (ref "C29") (pin "2") (pinfunction "2_2") (pintype "passive"))
      (node (ref "C9") (pin "2") (pinfunction "2_2") (pintype "passive"))
      (node (ref "J1") (pin "2") (pinfunction "2_2") (pintype "passive"))
      (node (ref "J2") (pin "1") (pinfunction "1_1") (pintype "passive"))
      (node (ref "J2") (pin "2") (pinfunction "2_2") (pintype "passive"))
      (node (ref "J4") (pin "2") (pinfunction "2_2") (pintype "passive"))
      (node (ref "LED1") (pin "2") (pinfunction "K_2") (pintype "passive"))
      (node (ref "NT1") (pin "2") (pinfunction "2_2") (pintype "passive"))
      (node (ref "NT2") (pin "2") (pinfunction "2_2") (pintype "passive"))
      (node (ref "NT3") (pin "2") (pinfunction "2_2") (pintype "passive"))
      (node (ref "P1") (pin "4") (pinfunction "4_4") (pintype "power_in"))
      (node (ref "P2") (pin "5") (pinfunction "5_5") (pintype "passive"))
      (node (ref "P3") (pin "3") (pinfunction "3_3") (pintype "passive"))
      (node (ref "P4") (pin "6") (pinfunction "GND_6") (pintype "passive"))
      (node (ref "P5") (pin "2") (pinfunction "GND_2") (pintype "passive"))
      (node (ref "P5") (pin "4") (pinfunction "GND_4") (pintype "passive"))
      (node (ref "R12") (pin "1") (pinfunction "1_1") (pintype "passive"))
      (node (ref "R8") (pin "1") (pinfunction "1_1") (pintype "passive"))
      (node (ref "S1") (pin "1") (pinfunction "1_1") (pintype "passive"))
      (node (ref "U1") (pin "26") (pinfunction "DVSS1_26") (pintype "power_in"))
      (node (ref "U1") (pin "51") (pinfunction "DVSS2_51") (pintype "power_in"))
      (node (ref "U1") (pin "75") (pinfunction "DVSS3_75") (pintype "power_in"))
      (node (ref "U1") (pin "99") (pinfunction "AVSS1_99") (pintype "power_in"))
      (node (ref "U2") (pin "2") (pinfunction "GND_2") (pintype "power_in"))
      (node (ref "U3") (pin "1") (pinfunction "PGND_1") (pintype "passive"))
      (node (ref "U3") (pin "3") (pinfunction "AGND_3") (pintype "passive"))
      (node (ref "U3") (pin "9") (pinfunction "PAD_9") (pintype "passive"))
    )
    (net (code "49") (name "TARGET_VCC") (class "Default")
      (node (ref "C11") (pin "1") (pinfunction "1_1") (pintype "passive"))
      (node (ref "C12") (pin "1") (pinfunction "1_1") (pintype "passive"))
      (node (ref "NT4") (pin "2") (pinfunction "2_2") (pintype "passive"))
      (node (ref "P1") (pin "1") (pinfunction "1_1") (pintype "power_in"))
      (node (ref "P4") (pin "7") (pinfunction "VTTL_7") (pintype "passive"))
      (node (ref "R6") (pin "2") (pinfunction "2_2") (pintype "passive"))
      (node (ref "U2") (pin "5") (pinfunction "OUT_5") (pintype "power_in"))
    )
    (net (code "50") (name "USSXTAL_GND") (class "Default")
      (node (ref "C7") (pin "2") (pinfunction "2_2") (pintype "passive"))
      (node (ref "C8") (pin "2") (pinfunction "2_2") (pintype "passive"))
      (node (ref "NT1") (pin "1") (pinfunction "1_1") (pintype "passive"))
      (node (ref "U1") (pin "96") (pinfunction "AVSS5_96") (pintype "power_in"))
      (node (ref "Y2") (pin "2") (pinfunction "GND_2") (pintype "passive"))
    )
    (net (code "51") (name "USS_GND") (class "Default")
      (node (ref "C13") (pin "2") (pinfunction "2_2") (pintype "passive"))
      (node (ref "C14") (pin "1") (pinfunction "1_1") (pintype "passive"))
      (node (ref "C20") (pin "1") (pinfunction "1_1") (pintype "passive"))
      (node (ref "C21") (pin "2") (pinfunction "2_2") (pintype "passive"))
      (node (ref "J3") (pin "2") (pinfunction "2_2") (pintype "passive"))
      (node (ref "J3") (pin "3") (pinfunction "3_3") (pintype "passive"))
      (node (ref "J3") (pin "4") (pinfunction "4_4") (pintype "passive"))
      (node (ref "J3") (pin "5") (pinfunction "5_5") (pintype "passive"))
      (node (ref "J3") (pin "6") (pinfunction "6_6") (pintype "passive"))
      (node (ref "J3") (pin "8") (pinfunction "8_8") (pintype "passive"))
      (node (ref "NT3") (pin "1") (pinfunction "1_1") (pintype "passive"))
      (node (ref "U1") (pin "87") (pinfunction "PVSS_87") (pintype "power_in"))
      (node (ref "U1") (pin "89") (pinfunction "PVSS_89") (pintype "power_in"))
    )
    (net (code "52") (name "XTAL_GND") (class "Default")
      (node (ref "C2") (pin "1") (pinfunction "1_1") (pintype "passive"))
      (node (ref "C3") (pin "2") (pinfunction "2_2") (pintype "passive"))
      (node (ref "C5") (pin "2") (pinfunction "2_2") (pintype "passive"))
      (node (ref "C6") (pin "2") (pinfunction "2_2") (pintype "passive"))
      (node (ref "NT2") (pin "1") (pinfunction "1_1") (pintype "passive"))
      (node (ref "U1") (pin "11") (pinfunction "AVSS4_11") (pintype "power_in"))
      (node (ref "U1") (pin "5") (pinfunction "AVSS2_5") (pintype "power_in"))
      (node (ref "U1") (pin "8") (pinfunction "AVSS3_8") (pintype "power_in"))
    )
    (net (code "53") (name "unconnected-(P4-5V-Pad8)") (class "Default")
      (node (ref "P4") (pin "8") (pinfunction "5V_8") (pintype "passive"))
    )
    (net (code "54") (name "unconnected-(P4-SPKN-Pad1)") (class "Default")
      (node (ref "P4") (pin "1") (pinfunction "SPKN_1") (pintype "passive"))
    )
    (net (code "55") (name "unconnected-(P4-SPKP-Pad2)") (class "Default")
      (node (ref "P4") (pin "2") (pinfunction "SPKP_2") (pintype "passive"))
    )
    (net (code "56") (name "unconnected-(P5-MICN-Pad8)") (class "Default")
      (node (ref "P5") (pin "8") (pinfunction "MICN_8") (pintype "passive"))
    )
    (net (code "57") (name "unconnected-(P5-MICP-Pad7)") (class "Default")
      (node (ref "P5") (pin "7") (pinfunction "MICP_7") (pintype "passive"))
    )
    (net (code "58") (name "unconnected-(U1-P1.0{slash}UCA1CLK{slash}TA1.0{slash}A0{slash}C0{slash}VREF-{slash}VEREF--Pad3)") (class "Default")
      (node (ref "U1") (pin "3") (pinfunction "P1.0/UCA1CLK/TA1.0/A0/C0/VREF-/VEREF-_3") (pintype "bidirectional"))
    )
    (net (code "59") (name "unconnected-(U1-P1.1{slash}UCA1STE{slash}TA4.0{slash}A1{slash}C1{slash}VREF+{slash}VEREF+-Pad4)") (class "Default")
      (node (ref "U1") (pin "4") (pinfunction "P1.1/UCA1STE/TA4.0/A1/C1/VREF+/VEREF+_4") (pintype "bidirectional"))
    )
    (net (code "60") (name "unconnected-(U1-P1.5{slash}TB0.5{slash}UCB0CLK{slash}A3{slash}C3-Pad13)") (class "Default")
      (node (ref "U1") (pin "13") (pinfunction "P1.5/TB0.5/UCB0CLK/A3/C3_13") (pintype "bidirectional"))
    )
    (net (code "61") (name "unconnected-(U1-P1.6{slash}UCB0SIMO{slash}UCB0SDA{slash}A4{slash}C4-Pad14)") (class "Default")
      (node (ref "U1") (pin "14") (pinfunction "P1.6/UCB0SIMO/UCB0SDA/A4/C4_14") (pintype "bidirectional"))
    )
    (net (code "62") (name "unconnected-(U1-P1.7{slash}UCB0SOMI{slash}UCB0SCL{slash}A5{slash}C5-Pad15)") (class "Default")
      (node (ref "U1") (pin "15") (pinfunction "P1.7/UCB0SOMI/UCB0SCL/A5/C5_15") (pintype "bidirectional"))
    )
    (net (code "63") (name "unconnected-(U1-P2.0{slash}UCA0SIMO{slash}UCA0TXD{slash}A6{slash}C6{slash}BSLTX-Pad16)") (class "Default")
      (node (ref "U1") (pin "16") (pinfunction "P2.0/UCA0SIMO/UCA0TXD/A6/C6/BSLTX_16") (pintype "bidirectional"))
    )
    (net (code "64") (name "unconnected-(U1-P2.1{slash}UCA0SOMI{slash}UCA0RXD{slash}A7{slash}C7{slash}BSLRX-Pad17)") (class "Default")
      (node (ref "U1") (pin "17") (pinfunction "P2.1/UCA0SOMI/UCA0RXD/A7/C7/BSLRX_17") (pintype "bidirectional"))
    )
    (net (code "65") (name "unconnected-(U1-P2.4{slash}TA0CLK{slash}TB0CLK{slash}TA1CLK{slash}LCDS32-Pad28)") (class "Default")
      (node (ref "U1") (pin "28") (pinfunction "P2.4/TA0CLK/TB0CLK/TA1CLK/LCDS32_28") (pintype "bidirectional"))
    )
    (net (code "66") (name "unconnected-(U1-P2.5{slash}TA4.0{slash}LCDS31-Pad29)") (class "Default")
      (node (ref "U1") (pin "29") (pinfunction "P2.5/TA4.0/LCDS31_29") (pintype "bidirectional"))
    )
    (net (code "67") (name "unconnected-(U1-P2.6{slash}TA4.1{slash}LCDS30-Pad30)") (class "Default")
      (node (ref "U1") (pin "30") (pinfunction "P2.6/TA4.1/LCDS30_30") (pintype "bidirectional"))
    )
    (net (code "68") (name "unconnected-(U1-P2.7{slash}TA0.0{slash}LCDS21-Pad39)") (class "Default")
      (node (ref "U1") (pin "39") (pinfunction "P2.7/TA0.0/LCDS21_39") (pintype "bidirectional"))
    )
    (net (code "69") (name "unconnected-(U1-P3.0{slash}TB0.0{slash}LCDS29-Pad31)") (class "Default")
      (node (ref "U1") (pin "31") (pinfunction "P3.0/TB0.0/LCDS29_31") (pintype "bidirectional"))
    )
    (net (code "70") (name "unconnected-(U1-P3.1{slash}TB0.1{slash}LCDS28-Pad32)") (class "Default")
      (node (ref "U1") (pin "32") (pinfunction "P3.1/TB0.1/LCDS28_32") (pintype "bidirectional"))
    )
    (net (code "71") (name "unconnected-(U1-P3.2{slash}TB0.2{slash}LCDS27-Pad33)") (class "Default")
      (node (ref "U1") (pin "33") (pinfunction "P3.2/TB0.2/LCDS27_33") (pintype "bidirectional"))
    )
    (net (code "72") (name "unconnected-(U1-P3.3{slash}TB0.3{slash}LCDS26-Pad34)") (class "Default")
      (node (ref "U1") (pin "34") (pinfunction "P3.3/TB0.3/LCDS26_34") (pintype "bidirectional"))
    )
    (net (code "73") (name "unconnected-(U1-P3.4{slash}TB0OUTH{slash}LCDS25-Pad35)") (class "Default")
      (node (ref "U1") (pin "35") (pinfunction "P3.4/TB0OUTH/LCDS25_35") (pintype "bidirectional"))
    )
    (net (code "74") (name "unconnected-(U1-P3.5{slash}TB0.4{slash}LCDS24-Pad36)") (class "Default")
      (node (ref "U1") (pin "36") (pinfunction "P3.5/TB0.4/LCDS24_36") (pintype "bidirectional"))
    )
    (net (code "75") (name "unconnected-(U1-P3.6{slash}TB0.5{slash}LCDS23-Pad37)") (class "Default")
      (node (ref "U1") (pin "37") (pinfunction "P3.6/TB0.5/LCDS23_37") (pintype "bidirectional"))
    )
    (net (code "76") (name "unconnected-(U1-P3.7{slash}TB0.6{slash}LCDS22-Pad38)") (class "Default")
      (node (ref "U1") (pin "38") (pinfunction "P3.7/TB0.6/LCDS22_38") (pintype "bidirectional"))
    )
    (net (code "77") (name "unconnected-(U1-P4.2{slash}UCA0STE{slash}LCDS14-Pad46)") (class "Default")
      (node (ref "U1") (pin "46") (pinfunction "P4.2/UCA0STE/LCDS14_46") (pintype "bidirectional"))
    )
    (net (code "78") (name "unconnected-(U1-P4.3{slash}UCA0SIMO{slash}UCA0TXD{slash}LCDS13-Pad47)") (class "Default")
      (node (ref "U1") (pin "47") (pinfunction "P4.3/UCA0SIMO/UCA0TXD/LCDS13_47") (pintype "bidirectional"))
    )
    (net (code "79") (name "unconnected-(U1-P4.4{slash}UCA0SOMI{slash}UCA0RXD{slash}LCDS12-Pad48)") (class "Default")
      (node (ref "U1") (pin "48") (pinfunction "P4.4/UCA0SOMI/UCA0RXD/LCDS12_48") (pintype "bidirectional"))
    )
    (net (code "80") (name "unconnected-(U1-P4.5{slash}TA0CLK{slash}TA1CLK{slash}LCDS11-Pad49)") (class "Default")
      (node (ref "U1") (pin "49") (pinfunction "P4.5/TA0CLK/TA1CLK/LCDS11_49") (pintype "bidirectional"))
    )
    (net (code "81") (name "unconnected-(U1-P4.6{slash}TB0CLK{slash}TA4CLK{slash}LCDS10-Pad50)") (class "Default")
      (node (ref "U1") (pin "50") (pinfunction "P4.6/TB0CLK/TA4CLK/LCDS10_50") (pintype "bidirectional"))
    )
    (net (code "82") (name "unconnected-(U1-P4.7{slash}DMAE0{slash}LCDS9-Pad53)") (class "Default")
      (node (ref "U1") (pin "53") (pinfunction "P4.7/DMAE0/LCDS9_53") (pintype "bidirectional"))
    )
    (net (code "83") (name "unconnected-(U1-P5.0{slash}UCA2SIMO{slash}UCA2TXD{slash}LCDS8-Pad54)") (class "Default")
      (node (ref "U1") (pin "54") (pinfunction "P5.0/UCA2SIMO/UCA2TXD/LCDS8_54") (pintype "bidirectional"))
    )
    (net (code "84") (name "unconnected-(U1-P5.1{slash}UCA2SOMI{slash}UCA2RXD{slash}LCDS7-Pad55)") (class "Default")
      (node (ref "U1") (pin "55") (pinfunction "P5.1/UCA2SOMI/UCA2RXD/LCDS7_55") (pintype "bidirectional"))
    )
    (net (code "85") (name "unconnected-(U1-P5.2{slash}UCA2CLK{slash}LCDS6-Pad56)") (class "Default")
      (node (ref "U1") (pin "56") (pinfunction "P5.2/UCA2CLK/LCDS6_56") (pintype "bidirectional"))
    )
    (net (code "86") (name "unconnected-(U1-P5.3{slash}UCA2STE{slash}LCDS5-Pad57)") (class "Default")
      (node (ref "U1") (pin "57") (pinfunction "P5.3/UCA2STE/LCDS5_57") (pintype "bidirectional"))
    )
    (net (code "87") (name "unconnected-(U1-P5.4{slash}UCB1CLK{slash}LCDS4-Pad58)") (class "Default")
      (node (ref "U1") (pin "58") (pinfunction "P5.4/UCB1CLK/LCDS4_58") (pintype "bidirectional"))
    )
    (net (code "88") (name "unconnected-(U1-P5.5{slash}TA0CLK{slash}UCB1SIMO{slash}UCB1SDA{slash}LCDS3-Pad59)") (class "Default")
      (node (ref "U1") (pin "59") (pinfunction "P5.5/TA0CLK/UCB1SIMO/UCB1SDA/LCDS3_59") (pintype "bidirectional"))
    )
    (net (code "89") (name "unconnected-(U1-P5.6{slash}UCB1SOMI{slash}UCB1SCL{slash}LCDS2-Pad60)") (class "Default")
      (node (ref "U1") (pin "60") (pinfunction "P5.6/UCB1SOMI/UCB1SCL/LCDS2_60") (pintype "bidirectional"))
    )
    (net (code "90") (name "unconnected-(U1-P5.7{slash}UCB1STE{slash}LCDS1-Pad61)") (class "Default")
      (node (ref "U1") (pin "61") (pinfunction "P5.7/UCB1STE/LCDS1_61") (pintype "bidirectional"))
    )
    (net (code "91") (name "unconnected-(U1-P6.0{slash}COUT{slash}LCDS0-Pad62)") (class "Default")
      (node (ref "U1") (pin "62") (pinfunction "P6.0/COUT/LCDS0_62") (pintype "bidirectional"))
    )
    (net (code "92") (name "unconnected-(U1-P6.1{slash}R03-Pad71)") (class "Default")
      (node (ref "U1") (pin "71") (pinfunction "P6.1/R03_71") (pintype "bidirectional"))
    )
    (net (code "93") (name "unconnected-(U1-P6.2{slash}R13{slash}LCDREF-Pad72)") (class "Default")
      (node (ref "U1") (pin "72") (pinfunction "P6.2/R13/LCDREF_72") (pintype "bidirectional"))
    )
    (net (code "94") (name "unconnected-(U1-P6.3{slash}R23-Pad73)") (class "Default")
      (node (ref "U1") (pin "73") (pinfunction "P6.3/R23_73") (pintype "bidirectional"))
    )
    (net (code "95") (name "unconnected-(U1-P6.4{slash}COM0-Pad63)") (class "Default")
      (node (ref "U1") (pin "63") (pinfunction "P6.4/COM0_63") (pintype "bidirectional"))
    )
    (net (code "96") (name "unconnected-(U1-P6.5{slash}COM1-Pad64)") (class "Default")
      (node (ref "U1") (pin "64") (pinfunction "P6.5/COM1_64") (pintype "bidirectional"))
    )
    (net (code "97") (name "unconnected-(U1-P6.6{slash}COM2{slash}LCDS38-Pad65)") (class "Default")
      (node (ref "U1") (pin "65") (pinfunction "P6.6/COM2/LCDS38_65") (pintype "bidirectional"))
    )
    (net (code "98") (name "unconnected-(U1-P6.7{slash}COM3{slash}LCDS37-Pad66)") (class "Default")
      (node (ref "U1") (pin "66") (pinfunction "P6.7/COM3/LCDS37_66") (pintype "bidirectional"))
    )
    (net (code "99") (name "unconnected-(U1-P7.0{slash}UCA2SIMO{slash}UCA2TXD{slash}ACLK{slash}COM4{slash}LCDS36-Pad67)") (class "Default")
      (node (ref "U1") (pin "67") (pinfunction "P7.0/UCA2SIMO/UCA2TXD/ACLK/COM4/LCDS36_67") (pintype "bidirectional"))
    )
    (net (code "100") (name "unconnected-(U1-P7.1{slash}UCA2SOMI{slash}UCA2RXD{slash}SMCLK{slash}COM5{slash}LCDS35-Pad68)") (class "Default")
      (node (ref "U1") (pin "68") (pinfunction "P7.1/UCA2SOMI/UCA2RXD/SMCLK/COM5/LCDS35_68") (pintype "bidirectional"))
    )
    (net (code "101") (name "unconnected-(U1-P7.2{slash}UCA2CLK{slash}TB0.0{slash}COM6{slash}LCDS34-Pad69)") (class "Default")
      (node (ref "U1") (pin "69") (pinfunction "P7.2/UCA2CLK/TB0.0/COM6/LCDS34_69") (pintype "bidirectional"))
    )
    (net (code "102") (name "unconnected-(U1-P7.3{slash}UCA2STE{slash}TB0.1{slash}COM7{slash}LCDS33-Pad70)") (class "Default")
      (node (ref "U1") (pin "70") (pinfunction "P7.3/UCA2STE/TB0.1/COM7/LCDS33_70") (pintype "bidirectional"))
    )
    (net (code "103") (name "unconnected-(U1-P7.4{slash}TA0.1{slash}MTIF_OUT_IN-Pad77)") (class "Default")
      (node (ref "U1") (pin "77") (pinfunction "P7.4/TA0.1/MTIF_OUT_IN_77") (pintype "bidirectional"))
    )
    (net (code "104") (name "unconnected-(U1-P7.5{slash}TA1.1{slash}MTIF_PIN_EN-Pad78)") (class "Default")
      (node (ref "U1") (pin "78") (pinfunction "P7.5/TA1.1/MTIF_PIN_EN_78") (pintype "bidirectional"))
    )
    (net (code "105") (name "unconnected-(U1-P7.6{slash}TA4.1{slash}DMAE0{slash}COUT-Pad83)") (class "Default")
      (node (ref "U1") (pin "83") (pinfunction "P7.6/TA4.1/DMAE0/COUT_83") (pintype "bidirectional"))
    )
    (net (code "106") (name "unconnected-(U1-P7.7{slash}TA0.2{slash}TB0OUTH{slash}COUT-Pad84)") (class "Default")
      (node (ref "U1") (pin "84") (pinfunction "P7.7/TA0.2/TB0OUTH/COUT_84") (pintype "bidirectional"))
    )
    (net (code "107") (name "unconnected-(U1-P8.0{slash}UCA3STE{slash}TB0.2{slash}DMAE0-Pad79)") (class "Default")
      (node (ref "U1") (pin "79") (pinfunction "P8.0/UCA3STE/TB0.2/DMAE0_79") (pintype "bidirectional"))
    )
    (net (code "108") (name "unconnected-(U1-PJ.0{slash}TDO{slash}ACLK{slash}SRSCG1{slash}DMAE0{slash}C10-Pad22)") (class "Default")
      (node (ref "U1") (pin "22") (pinfunction "PJ.0/TDO/ACLK/SRSCG1/DMAE0/C10_22") (pintype "bidirectional"))
    )
    (net (code "109") (name "unconnected-(U1-PJ.1{slash}TDI{slash}TCLK{slash}SMCLK{slash}SRSCG0{slash}TA4CLK{slash}C11-Pad23)") (class "Default")
      (node (ref "U1") (pin "23") (pinfunction "PJ.1/TDI/TCLK/SMCLK/SRSCG0/TA4CLK/C11_23") (pintype "bidirectional"))
    )
    (net (code "110") (name "unconnected-(U1-PJ.2{slash}TMS{slash}MCLK{slash}SROSCOFF{slash}TB0OUTH{slash}C12-Pad24)") (class "Default")
      (node (ref "U1") (pin "24") (pinfunction "PJ.2/TMS/MCLK/SROSCOFF/TB0OUTH/C12_24") (pintype "bidirectional"))
    )
    (net (code "111") (name "unconnected-(U1-PJ.3{slash}TCK{slash}RTCCLK{slash}SRCPUOFF{slash}TB0.6{slash}C13-Pad25)") (class "Default")
      (node (ref "U1") (pin "25") (pinfunction "PJ.3/TCK/RTCCLK/SRCPUOFF/TB0.6/C13_25") (pintype "bidirectional"))
    )
    (net (code "112") (name "unconnected-(U1-R33{slash}LCDCAP-Pad74)") (class "Default")
      (node (ref "U1") (pin "74") (pinfunction "R33/LCDCAP_74") (pintype "bidirectional"))
    )
  )
)
